# Differential_Pair_Setup.net
KiCad netlist of a schematic drawn in Altium Designer
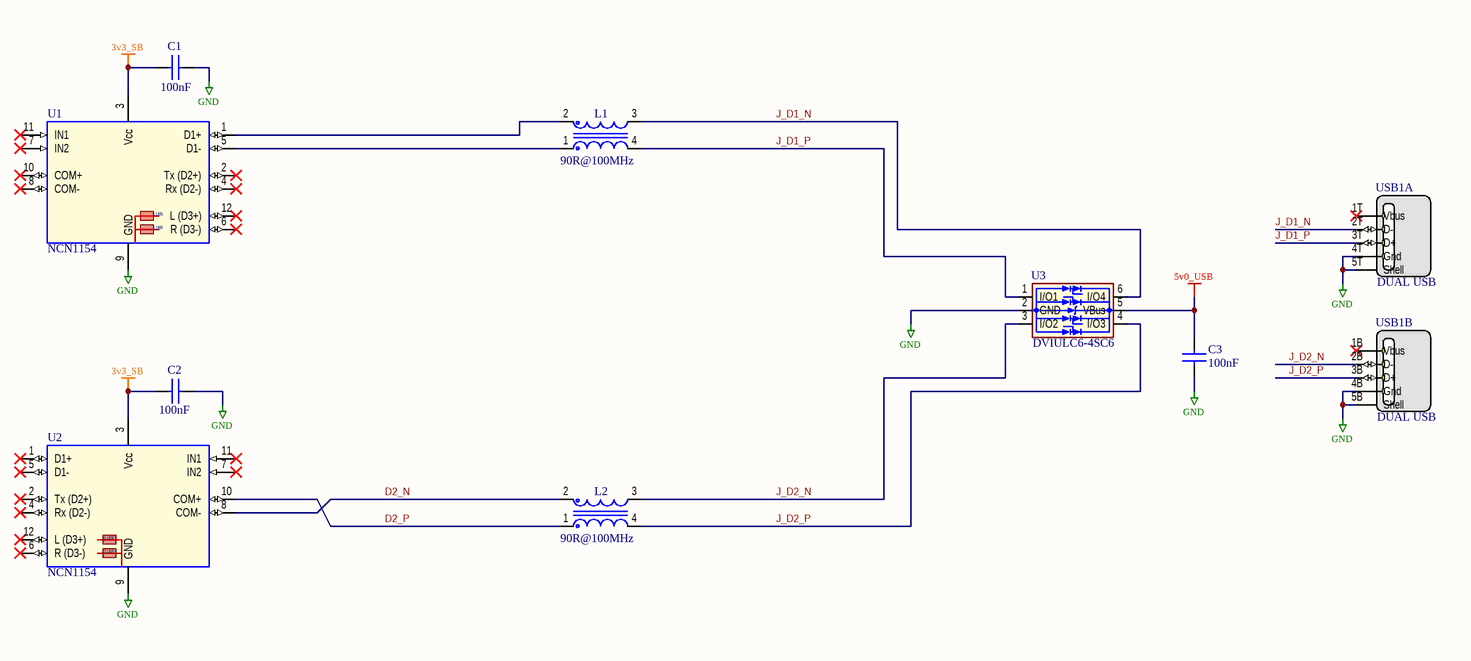
[diagram p0: Differential Pair Setup.SchDoc]

(export (version "E")
  (design (tool "Eeschema 10.0.6"))
  (components
    (comp (ref "C1")
      (value "100nF")
      (footprint "CC0402")
      (description "Cap, 100nF, X7R, 16V, ±10%, CC0402")
      (libsource (lib "xSignal_Differential_Pairs") (part "CAP_100nF"))
    )
    (comp (ref "C2")
      (value "100nF")
      (footprint "CC0402")
      (description "Cap, 100nF, X7R, 16V, ±10%, CC0402")
      (libsource (lib "xSignal_Differential_Pairs") (part "CAP_100nF"))
    )
    (comp (ref "C3")
      (value "100nF")
      (footprint "CC0402")
      (description "Cap, 100nF, X7R, 16V, ±10%, CC0402")
      (libsource (lib "xSignal_Differential_Pairs") (part "CAP_100nF"))
    )
    (comp (ref "L1")
      (value "90R@100MHz")
      (footprint "ACM2012")
      (description "CMNCK, 90R@100MHz, 50V, 400mA, ACM2012")
      (libsource (lib "xSignal_Differential_Pairs") (part "FILTER"))
    )
    (comp (ref "L2")
      (value "90R@100MHz")
      (footprint "ACM2012")
      (description "CMNCK, 90R@100MHz, 50V, 400mA, ACM2012")
      (libsource (lib "xSignal_Differential_Pairs") (part "FILTER"))
    )
    (comp (ref "U1")
      (value "NCN1154")
      (footprint "UQFN12")
      (description "3:1 High-Speed USB /UART/Auido Mux")
      (libsource (lib "") (part "USB_UART_1"))
    )
    (comp (ref "U2")
      (value "NCN1154")
      (footprint "UQFN12")
      (description "3:1 High-Speed USB /UART/Auido Mux")
      (libsource (lib "xSignal_Differential_Pairs") (part "USB_UART"))
    )
    (comp (ref "U3")
      (value "DVIULC6-4SC6")
      (footprint "SOT23-6L")
      (description "4-chl Ultra-Low Capacitance ESD protector with TVS diode")
      (libsource (lib "xSignal_Differential_Pairs") (part "ESD_Protector"))
    )
    (comp (ref "USB1")
      (value "DUAL USB")
      (footprint "USB-A_RA_DUAL")
      (libsource (lib "xSignal_Differential_Pairs") (part "USB"))
    )
  )
  (nets
    (net (code "1") (name "/D2_N") (class "Default")
      (node (ref "L2") (pin "2") (pinfunction "2_2") (pintype "passive"))
      (node (ref "U2") (pin "8") (pinfunction "COM-_8") (pintype "bidirectional"))
    )
    (net (code "2") (name "/D2_P") (class "Default")
      (node (ref "L2") (pin "1") (pinfunction "1_1") (pintype "passive"))
      (node (ref "U2") (pin "10") (pinfunction "COM+_10") (pintype "bidirectional"))
    )
    (net (code "3") (name "/J_D1_N") (class "Default")
      (node (ref "L1") (pin "3") (pinfunction "3_3") (pintype "passive"))
      (node (ref "U3") (pin "6") (pinfunction "I/O4_6") (pintype "passive"))
      (node (ref "USB1") (pin "2T") (pinfunction "D-_2T") (pintype "bidirectional"))
    )
    (net (code "4") (name "/J_D1_P") (class "Default")
      (node (ref "L1") (pin "4") (pinfunction "4_4") (pintype "passive"))
      (node (ref "U3") (pin "1") (pinfunction "I/O1_1") (pintype "passive"))
      (node (ref "USB1") (pin "3T") (pinfunction "D+_3T") (pintype "bidirectional"))
    )
    (net (code "5") (name "/J_D2_N") (class "Default")
      (node (ref "L2") (pin "3") (pinfunction "3_3") (pintype "passive"))
      (node (ref "U3") (pin "3") (pinfunction "I/O2_3") (pintype "passive"))
      (node (ref "USB1") (pin "2B") (pinfunction "D-_2B") (pintype "bidirectional"))
    )
    (net (code "6") (name "/J_D2_P") (class "Default")
      (node (ref "L2") (pin "4") (pinfunction "4_4") (pintype "passive"))
      (node (ref "U3") (pin "4") (pinfunction "I/O3_4") (pintype "passive"))
      (node (ref "USB1") (pin "3B") (pinfunction "D+_3B") (pintype "bidirectional"))
    )
    (net (code "7") (name "3v3_SB") (class "Default")
      (node (ref "C1") (pin "2") (pinfunction "2_2") (pintype "passive"))
      (node (ref "C2") (pin "2") (pinfunction "2_2") (pintype "passive"))
      (node (ref "U1") (pin "3") (pinfunction "Vcc_3") (pintype "power_in"))
      (node (ref "U2") (pin "3") (pinfunction "Vcc_3") (pintype "power_in"))
    )
    (net (code "8") (name "5v0_USB") (class "Default")
      (node (ref "C3") (pin "1") (pinfunction "1_1") (pintype "passive"))
      (node (ref "U3") (pin "5") (pinfunction "VBus_5") (pintype "passive"))
    )
    (net (code "9") (name "GND") (class "Default")
      (node (ref "C1") (pin "1") (pinfunction "1_1") (pintype "passive"))
      (node (ref "C2") (pin "1") (pinfunction "1_1") (pintype "passive"))
      (node (ref "C3") (pin "2") (pinfunction "2_2") (pintype "passive"))
      (node (ref "U1") (pin "9") (pinfunction "GND_9") (pintype "power_in"))
      (node (ref "U2") (pin "9") (pinfunction "GND_9") (pintype "power_in"))
      (node (ref "U3") (pin "2") (pinfunction "GND_2") (pintype "passive"))
      (node (ref "USB1") (pin "4B") (pinfunction "Gnd_4B") (pintype "power_in"))
      (node (ref "USB1") (pin "4T") (pinfunction "Gnd_4T") (pintype "power_in"))
      (node (ref "USB1") (pin "5B") (pinfunction "Shell_5B") (pintype "power_in"))
      (node (ref "USB1") (pin "5T") (pinfunction "Shell_5T") (pintype "power_in"))
    )
    (net (code "10") (name "Net-(U1-D1+)") (class "Default")
      (node (ref "L1") (pin "2") (pinfunction "2_2") (pintype "passive"))
      (node (ref "U1") (pin "1") (pinfunction "D1+_1") (pintype "bidirectional"))
    )
    (net (code "11") (name "Net-(U1-D1-)") (class "Default")
      (node (ref "L1") (pin "1") (pinfunction "1_1") (pintype "passive"))
      (node (ref "U1") (pin "5") (pinfunction "D1-_5") (pintype "bidirectional"))
    )
    (net (code "12") (name "unconnected-(U1-COM+-Pad10)") (class "Default")
      (node (ref "U1") (pin "10") (pinfunction "COM+_10") (pintype "bidirectional+no_connect"))
    )
    (net (code "13") (name "unconnected-(U1-COM--Pad8)") (class "Default")
      (node (ref "U1") (pin "8") (pinfunction "COM-_8") (pintype "bidirectional+no_connect"))
    )
    (net (code "14") (name "unconnected-(U1-IN1-Pad11)") (class "Default")
      (node (ref "U1") (pin "11") (pinfunction "IN1_11") (pintype "input+no_connect"))
    )
    (net (code "15") (name "unconnected-(U1-IN2-Pad7)") (class "Default")
      (node (ref "U1") (pin "7") (pinfunction "IN2_7") (pintype "input+no_connect"))
    )
    (net (code "16") (name "unconnected-(U1-L_(D3+)-Pad12)") (class "Default")
      (node (ref "U1") (pin "12") (pinfunction "L_(D3+)_12") (pintype "bidirectional+no_connect"))
    )
    (net (code "17") (name "unconnected-(U1-R_(D3-)-Pad6)") (class "Default")
      (node (ref "U1") (pin "6") (pinfunction "R_(D3-)_6") (pintype "bidirectional+no_connect"))
    )
    (net (code "18") (name "unconnected-(U1-Rx_(D2-)-Pad4)") (class "Default")
      (node (ref "U1") (pin "4") (pinfunction "Rx_(D2-)_4") (pintype "bidirectional+no_connect"))
    )
    (net (code "19") (name "unconnected-(U1-Tx_(D2+)-Pad2)") (class "Default")
      (node (ref "U1") (pin "2") (pinfunction "Tx_(D2+)_2") (pintype "bidirectional+no_connect"))
    )
    (net (code "20") (name "unconnected-(U2-D1+-Pad1)") (class "Default")
      (node (ref "U2") (pin "1") (pinfunction "D1+_1") (pintype "bidirectional+no_connect"))
    )
    (net (code "21") (name "unconnected-(U2-D1--Pad5)") (class "Default")
      (node (ref "U2") (pin "5") (pinfunction "D1-_5") (pintype "bidirectional+no_connect"))
    )
    (net (code "22") (name "unconnected-(U2-IN1-Pad11)") (class "Default")
      (node (ref "U2") (pin "11") (pinfunction "IN1_11") (pintype "input+no_connect"))
    )
    (net (code "23") (name "unconnected-(U2-IN2-Pad7)") (class "Default")
      (node (ref "U2") (pin "7") (pinfunction "IN2_7") (pintype "input+no_connect"))
    )
    (net (code "24") (name "unconnected-(U2-L_(D3+)-Pad12)") (class "Default")
      (node (ref "U2") (pin "12") (pinfunction "L_(D3+)_12") (pintype "bidirectional+no_connect"))
    )
    (net (code "25") (name "unconnected-(U2-R_(D3-)-Pad6)") (class "Default")
      (node (ref "U2") (pin "6") (pinfunction "R_(D3-)_6") (pintype "bidirectional+no_connect"))
    )
    (net (code "26") (name "unconnected-(U2-Rx_(D2-)-Pad4)") (class "Default")
      (node (ref "U2") (pin "4") (pinfunction "Rx_(D2-)_4") (pintype "bidirectional+no_connect"))
    )
    (net (code "27") (name "unconnected-(U2-Tx_(D2+)-Pad2)") (class "Default")
      (node (ref "U2") (pin "2") (pinfunction "Tx_(D2+)_2") (pintype "bidirectional+no_connect"))
    )
    (net (code "28") (name "unconnected-(USB1A-Vbus-Pad1T)") (class "Default")
      (node (ref "USB1") (pin "1T") (pinfunction "Vbus_1T") (pintype "power_in+no_connect"))
    )
    (net (code "29") (name "unconnected-(USB1B-Vbus-Pad1B)") (class "Default")
      (node (ref "USB1") (pin "1B") (pinfunction "Vbus_1B") (pintype "power_in+no_connect"))
    )
  )
)
